# Sheet1.net
KiCad netlist of a schematic drawn in Altium Designer
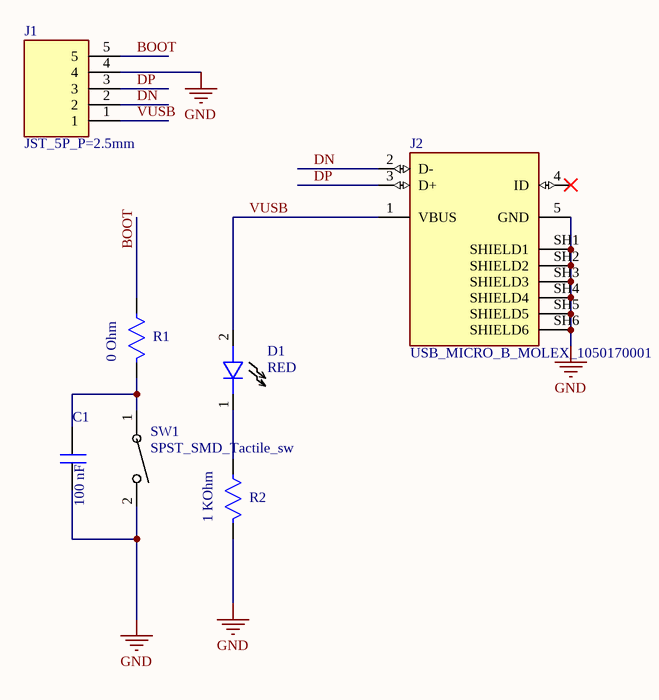
[diagram p0: Sheet1.SchDoc]

(export (version "E")
  (design (tool "Eeschema 10.0.6"))
  (components
    (comp (ref "C1")
      (value "100 nF")
      (footprint "CAP_0603")
      (description "Cap SMD.")
      (libsource (lib "Aptinex_discrete") (part "Cap SMD"))
    )
    (comp (ref "D1")
      (value "RED")
      (footprint "LED SMD 0603")
      (description "SMD LED")
      (libsource (lib "Aptinex_discrete") (part "LED SMD"))
    )
    (comp (ref "J1")
      (value "JST_5P_P=2.5mm")
      (footprint "JST_5P_P=2.5mm")
      (description "JST 1X5P , p=2.5mm XH connector, 5 way , Straight")
      (fields (field (name "MANUFACTURER_PART_NUMBER") "B5B-XH-A(LF)(SN)"))
      (libsource (lib "Aptinex_connectors") (part "JST_5P_P=2.5mm"))
    )
    (comp (ref "J2")
      (value "USB_MICRO_B_MOLEX_1050170001")
      (footprint "USB_MICRO_B_MOLEX_1050170001")
      (description "USB - micro B USB 2.0 Receptacle Connector 5 Position Surface Mount, Right Angle; Through Hole")
      (fields (field (name "MF") "Molex") (field (name "MP") "1050170001"))
      (libsource (lib "Aptinex_connectors") (part "USB_MICRO_B_MOLEX_1050170001"))
    )
    (comp (ref "R1")
      (value "0 Ohm")
      (footprint "Res_0603")
      (description "SMD Resistor")
      (fields (field (name "MP") "RC0805FR-07330RL") (field (name "MF") "Yageo"))
      (libsource (lib "Aptinex_discrete") (part "Res smd"))
    )
    (comp (ref "R2")
      (value "1 KOhm")
      (footprint "Res_0603")
      (description "SMD Resistor")
      (fields (field (name "MP") "RC0805FR-07330RL") (field (name "MF") "Yageo"))
      (libsource (lib "Aptinex_discrete") (part "Res smd"))
    )
    (comp (ref "SW1")
      (value "SPST_SMD_Tactile_sw")
      (footprint "SPST_SMD_6mm")
      (description "SPST SMD Tactile Switches Rectangle button Brick nogging")
      (libsource (lib "Aptinex_discrete") (part "SPST_SMD_Tactile_sw"))
    )
  )
  (nets
    (net (code "1") (name "/BOOT") (class "Default")
      (node (ref "J1") (pin "5") (pinfunction "5_5") (pintype "passive"))
      (node (ref "R1") (pin "2") (pinfunction "2_2") (pintype "passive"))
    )
    (net (code "2") (name "/DN") (class "Default")
      (node (ref "J1") (pin "2") (pinfunction "2_2") (pintype "passive"))
      (node (ref "J2") (pin "2") (pinfunction "D-_2") (pintype "bidirectional"))
    )
    (net (code "3") (name "/DP") (class "Default")
      (node (ref "J1") (pin "3") (pinfunction "3_3") (pintype "passive"))
      (node (ref "J2") (pin "3") (pinfunction "D+_3") (pintype "bidirectional"))
    )
    (net (code "4") (name "/VUSB") (class "Default")
      (node (ref "D1") (pin "2") (pinfunction "2_2") (pintype "passive"))
      (node (ref "J1") (pin "1") (pinfunction "1_1") (pintype "passive"))
      (node (ref "J2") (pin "1") (pinfunction "VBUS_1") (pintype "power_in"))
    )
    (net (code "5") (name "GND") (class "Default")
      (node (ref "C1") (pin "1") (pinfunction "1_1") (pintype "passive"))
      (node (ref "J1") (pin "4") (pinfunction "4_4") (pintype "passive"))
      (node (ref "J2") (pin "5") (pinfunction "GND_5") (pintype "power_in"))
      (node (ref "J2") (pin "SH1") (pinfunction "SHIELD1_SH1") (pintype "passive"))
      (node (ref "J2") (pin "SH2") (pinfunction "SHIELD2_SH2") (pintype "passive"))
      (node (ref "J2") (pin "SH3") (pinfunction "SHIELD3_SH3") (pintype "passive"))
      (node (ref "J2") (pin "SH4") (pinfunction "SHIELD4_SH4") (pintype "passive"))
      (node (ref "J2") (pin "SH5") (pinfunction "SHIELD5_SH5") (pintype "passive"))
      (node (ref "J2") (pin "SH6") (pinfunction "SHIELD6_SH6") (pintype "passive"))
      (node (ref "R2") (pin "1") (pinfunction "1_1") (pintype "passive"))
      (node (ref "SW1") (pin "2") (pinfunction "2_2") (pintype "passive"))
    )
    (net (code "6") (name "Net-(C1-Pad2)") (class "Default")
      (node (ref "C1") (pin "2") (pinfunction "2_2") (pintype "passive"))
      (node (ref "R1") (pin "1") (pinfunction "1_1") (pintype "passive"))
      (node (ref "SW1") (pin "1") (pinfunction "1_1") (pintype "passive"))
    )
    (net (code "7") (name "Net-(D1-Pad1)") (class "Default")
      (node (ref "D1") (pin "1") (pinfunction "1_1") (pintype "passive"))
      (node (ref "R2") (pin "2") (pinfunction "2_2") (pintype "passive"))
    )
    (net (code "8") (name "unconnected-(J2-ID-Pad4)") (class "Default")
      (node (ref "J2") (pin "4") (pinfunction "ID_4") (pintype "bidirectional+no_connect"))
    )
  )
)
